# POWER.net
KiCad netlist of a schematic drawn in Altium Designer
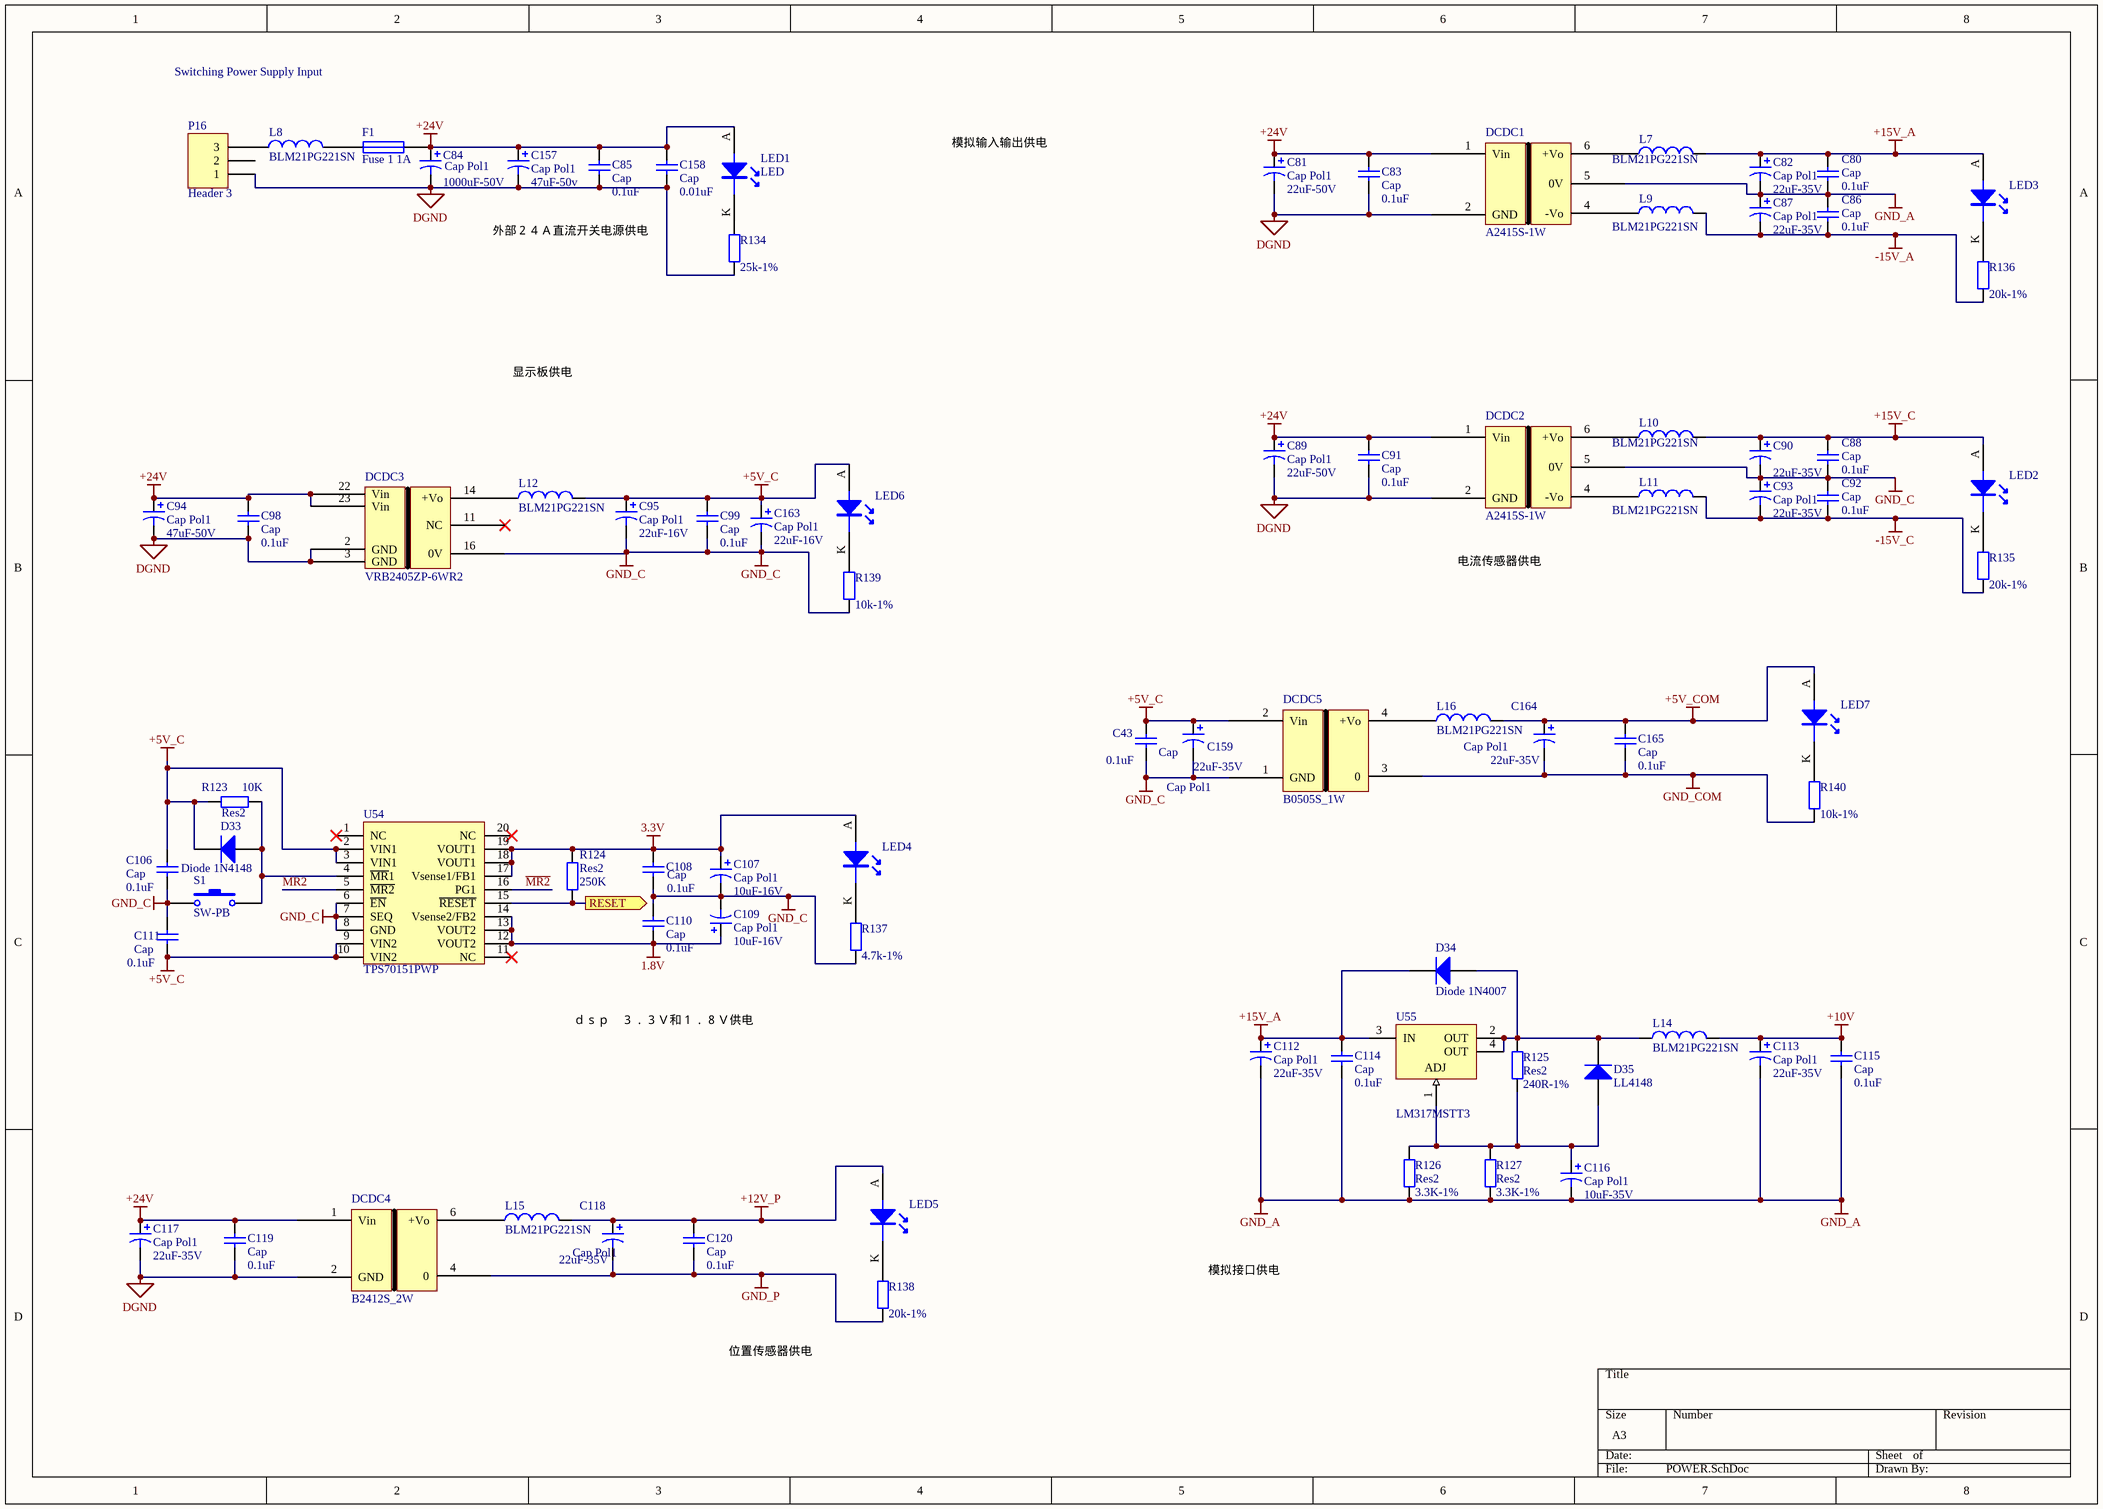
[diagram p0: POWER.SchDoc]

(export (version "E")
  (design (tool "Eeschema 10.0.6"))
  (components
    (comp (ref "C43")
      (value "Cap")
      (footprint "1206")
      (description "Capacitor")
      (fields (field (name "ALTIUM_VALUE") "0.1uF") (field (name "PUBLISHER") "Altium Limited"))
      (libsource (lib "Miscellaneous Devices") (part "Cap"))
    )
    (comp (ref "C80")
      (value "Cap")
      (footprint "1206")
      (description "Capacitor")
      (fields (field (name "ALTIUM_VALUE") "0.1uF") (field (name "PUBLISHER") "Altium Limited"))
      (libsource (lib "Miscellaneous Devices") (part "Cap"))
    )
    (comp (ref "C81")
      (value "Cap Pol1")
      (footprint "7343")
      (description "Polarized Capacitor (Radial)")
      (fields (field (name "ALTIUM_VALUE") "22uF-50V") (field (name "PUBLISHER") "Altium Limited"))
      (libsource (lib "Miscellaneous Devices") (part "Cap Pol1"))
    )
    (comp (ref "C82")
      (value "Cap Pol1")
      (footprint "7343")
      (description "Polarized Capacitor (Radial)")
      (fields (field (name "ALTIUM_VALUE") "22uF-35V") (field (name "PUBLISHER") "Altium Limited"))
      (libsource (lib "Miscellaneous Devices") (part "Cap Pol1"))
    )
    (comp (ref "C83")
      (value "Cap")
      (footprint "1206")
      (description "Capacitor")
      (fields (field (name "ALTIUM_VALUE") "0.1uF") (field (name "PUBLISHER") "Altium Limited"))
      (libsource (lib "Miscellaneous Devices") (part "Cap"))
    )
    (comp (ref "C84")
      (value "Cap Pol1")
      (footprint "电解电容1000uF")
      (description "Polarized Capacitor (Radial)")
      (fields (field (name "ALTIUM_VALUE") "1000uF-50V") (field (name "PUBLISHER") "Altium Limited"))
      (libsource (lib "Miscellaneous Devices") (part "Cap Pol1"))
    )
    (comp (ref "C85")
      (value "Cap")
      (footprint "1206")
      (description "Capacitor")
      (fields (field (name "ALTIUM_VALUE") "0.1uF") (field (name "PUBLISHER") "Altium Limited"))
      (libsource (lib "Miscellaneous Devices") (part "Cap"))
    )
    (comp (ref "C86")
      (value "Cap")
      (footprint "1206")
      (description "Capacitor")
      (fields (field (name "ALTIUM_VALUE") "0.1uF") (field (name "PUBLISHER") "Altium Limited"))
      (libsource (lib "Miscellaneous Devices") (part "Cap"))
    )
    (comp (ref "C87")
      (value "Cap Pol1")
      (footprint "7343")
      (description "Polarized Capacitor (Radial)")
      (fields (field (name "ALTIUM_VALUE") "22uF-35V") (field (name "PUBLISHER") "Altium Limited"))
      (libsource (lib "Miscellaneous Devices") (part "Cap Pol1"))
    )
    (comp (ref "C88")
      (value "Cap")
      (footprint "1206")
      (description "Capacitor")
      (fields (field (name "ALTIUM_VALUE") "0.1uF") (field (name "PUBLISHER") "Altium Limited"))
      (libsource (lib "Miscellaneous Devices") (part "Cap"))
    )
    (comp (ref "C89")
      (value "Cap Pol1")
      (footprint "7343")
      (description "Polarized Capacitor (Radial)")
      (fields (field (name "ALTIUM_VALUE") "22uF-50V") (field (name "PUBLISHER") "Altium Limited"))
      (libsource (lib "Miscellaneous Devices") (part "Cap Pol1"))
    )
    (comp (ref "C90")
      (value "22uF-35V")
      (footprint "7343")
      (description "Polarized Capacitor (Radial)")
      (fields (field (name "Comment") "Cap Pol1") (field (name "PUBLISHER") "Altium Limited"))
      (libsource (lib "Miscellaneous Devices") (part "Cap Pol1"))
    )
    (comp (ref "C91")
      (value "Cap")
      (footprint "1206")
      (description "Capacitor")
      (fields (field (name "ALTIUM_VALUE") "0.1uF") (field (name "PUBLISHER") "Altium Limited"))
      (libsource (lib "Miscellaneous Devices") (part "Cap"))
    )
    (comp (ref "C92")
      (value "Cap")
      (footprint "1206")
      (description "Capacitor")
      (fields (field (name "ALTIUM_VALUE") "0.1uF") (field (name "PUBLISHER") "Altium Limited"))
      (libsource (lib "Miscellaneous Devices") (part "Cap"))
    )
    (comp (ref "C93")
      (value "Cap Pol1")
      (footprint "7343")
      (description "Polarized Capacitor (Radial)")
      (fields (field (name "ALTIUM_VALUE") "22uF-35V") (field (name "PUBLISHER") "Altium Limited"))
      (libsource (lib "Miscellaneous Devices") (part "Cap Pol1"))
    )
    (comp (ref "C94")
      (value "Cap Pol1")
      (footprint "电解电容47uf")
      (description "Polarized Capacitor (Radial)")
      (fields (field (name "ALTIUM_VALUE") "47uF-50V") (field (name "PUBLISHER") "Altium Limited"))
      (libsource (lib "Miscellaneous Devices") (part "Cap Pol1"))
    )
    (comp (ref "C95")
      (value "Cap Pol1")
      (footprint "7343")
      (description "Polarized Capacitor (Radial)")
      (fields (field (name "ALTIUM_VALUE") "22uF-16V") (field (name "PUBLISHER") "Altium Limited"))
      (libsource (lib "Miscellaneous Devices") (part "Cap Pol1"))
    )
    (comp (ref "C98")
      (value "Cap")
      (footprint "1206")
      (description "Capacitor")
      (fields (field (name "ALTIUM_VALUE") "0.1uF") (field (name "PUBLISHER") "Altium Limited"))
      (libsource (lib "Miscellaneous Devices") (part "Cap"))
    )
    (comp (ref "C99")
      (value "Cap")
      (footprint "1206")
      (description "Capacitor")
      (fields (field (name "ALTIUM_VALUE") "0.1uF") (field (name "PUBLISHER") "Altium Limited"))
      (libsource (lib "Miscellaneous Devices") (part "Cap"))
    )
    (comp (ref "C106")
      (value "Cap")
      (footprint "1206")
      (description "Capacitor")
      (fields (field (name "ALTIUM_VALUE") "0.1uF") (field (name "PUBLISHER") "Altium Limited"))
      (libsource (lib "Miscellaneous Devices") (part "Cap"))
    )
    (comp (ref "C107")
      (value "Cap Pol1")
      (footprint "KEMET Electronics Footprints:1206")
      (description "Polarized Capacitor (Radial)")
      (fields (field (name "ALTIUM_VALUE") "10uF-16V") (field (name "PUBLISHER") "Altium Limited"))
      (libsource (lib "Miscellaneous Devices") (part "Cap Pol1"))
    )
    (comp (ref "C108")
      (value "Cap")
      (footprint "1206")
      (description "Capacitor")
      (fields (field (name "ALTIUM_VALUE") "0.1uF") (field (name "PUBLISHER") "Altium Limited"))
      (libsource (lib "Miscellaneous Devices") (part "Cap"))
    )
    (comp (ref "C109")
      (value "Cap Pol1")
      (footprint "KEMET Electronics Footprints:1206")
      (description "Polarized Capacitor (Radial)")
      (fields (field (name "ALTIUM_VALUE") "10uF-16V") (field (name "PUBLISHER") "Altium Limited"))
      (libsource (lib "Miscellaneous Devices") (part "Cap Pol1"))
    )
    (comp (ref "C110")
      (value "Cap")
      (footprint "1206")
      (description "Capacitor")
      (fields (field (name "ALTIUM_VALUE") "0.1uF") (field (name "PUBLISHER") "Altium Limited"))
      (libsource (lib "Miscellaneous Devices") (part "Cap"))
    )
    (comp (ref "C111")
      (value "Cap")
      (footprint "1206")
      (description "Capacitor")
      (fields (field (name "ALTIUM_VALUE") "0.1uF") (field (name "PUBLISHER") "Altium Limited"))
      (libsource (lib "Miscellaneous Devices") (part "Cap"))
    )
    (comp (ref "C112")
      (value "Cap Pol1")
      (footprint "7343")
      (description "Polarized Capacitor (Radial)")
      (fields (field (name "ALTIUM_VALUE") "22uF-35V") (field (name "PUBLISHER") "Altium Limited"))
      (libsource (lib "Miscellaneous Devices") (part "Cap Pol1"))
    )
    (comp (ref "C113")
      (value "Cap Pol1")
      (footprint "7343")
      (description "Polarized Capacitor (Radial)")
      (fields (field (name "ALTIUM_VALUE") "22uF-35V") (field (name "PUBLISHER") "Altium Limited"))
      (libsource (lib "Miscellaneous Devices") (part "Cap Pol1"))
    )
    (comp (ref "C114")
      (value "Cap")
      (footprint "1206")
      (description "Capacitor")
      (fields (field (name "ALTIUM_VALUE") "0.1uF") (field (name "PUBLISHER") "Altium Limited"))
      (libsource (lib "Miscellaneous Devices") (part "Cap"))
    )
    (comp (ref "C115")
      (value "Cap")
      (footprint "1206")
      (description "Capacitor")
      (fields (field (name "ALTIUM_VALUE") "0.1uF") (field (name "PUBLISHER") "Altium Limited"))
      (libsource (lib "Miscellaneous Devices") (part "Cap"))
    )
    (comp (ref "C116")
      (value "Cap Pol1")
      (footprint "KEMET Electronics Footprints:1206")
      (description "Polarized Capacitor (Radial)")
      (fields (field (name "ALTIUM_VALUE") "10uF-35V") (field (name "PUBLISHER") "Altium Limited"))
      (libsource (lib "Miscellaneous Devices") (part "Cap Pol1"))
    )
    (comp (ref "C117")
      (value "Cap Pol1")
      (footprint "7343")
      (description "Polarized Capacitor (Radial)")
      (fields (field (name "ALTIUM_VALUE") "22uF-35V") (field (name "PUBLISHER") "Altium Limited"))
      (libsource (lib "Miscellaneous Devices") (part "Cap Pol1"))
    )
    (comp (ref "C118")
      (value "Cap Pol1")
      (footprint "7343")
      (description "Polarized Capacitor (Radial)")
      (fields (field (name "ALTIUM_VALUE") "22uF-35V") (field (name "PUBLISHER") "Altium Limited"))
      (libsource (lib "Miscellaneous Devices") (part "Cap Pol1"))
    )
    (comp (ref "C119")
      (value "Cap")
      (footprint "1206")
      (description "Capacitor")
      (fields (field (name "ALTIUM_VALUE") "0.1uF") (field (name "PUBLISHER") "Altium Limited"))
      (libsource (lib "Miscellaneous Devices") (part "Cap"))
    )
    (comp (ref "C120")
      (value "Cap")
      (footprint "1206")
      (description "Capacitor")
      (fields (field (name "ALTIUM_VALUE") "0.1uF") (field (name "PUBLISHER") "Altium Limited"))
      (libsource (lib "Miscellaneous Devices") (part "Cap"))
    )
    (comp (ref "C157")
      (value "Cap Pol1")
      (footprint "电解电容47uf")
      (description "Polarized Capacitor (Radial)")
      (fields (field (name "ALTIUM_VALUE") "47uF-50v") (field (name "PUBLISHER") "Altium Limited"))
      (libsource (lib "Miscellaneous Devices") (part "Cap Pol1"))
    )
    (comp (ref "C158")
      (value "Cap")
      (footprint "1206")
      (description "Capacitor")
      (fields (field (name "ALTIUM_VALUE") "0.01uF") (field (name "PUBLISHER") "Altium Limited"))
      (libsource (lib "Miscellaneous Devices") (part "Cap"))
    )
    (comp (ref "C159")
      (value "Cap Pol1")
      (footprint "7343")
      (description "Polarized Capacitor (Radial)")
      (fields (field (name "ALTIUM_VALUE") "22uF-35V") (field (name "PUBLISHER") "Altium Limited"))
      (libsource (lib "Miscellaneous Devices") (part "Cap Pol1"))
    )
    (comp (ref "C163")
      (value "Cap Pol1")
      (footprint "7343")
      (description "Polarized Capacitor (Radial)")
      (fields (field (name "ALTIUM_VALUE") "22uF-16V") (field (name "PUBLISHER") "Altium Limited"))
      (libsource (lib "Miscellaneous Devices") (part "Cap Pol1"))
    )
    (comp (ref "C164")
      (value "Cap Pol1")
      (footprint "7343")
      (description "Polarized Capacitor (Radial)")
      (fields (field (name "ALTIUM_VALUE") "22uF-35V") (field (name "PUBLISHER") "Altium Limited"))
      (libsource (lib "Miscellaneous Devices") (part "Cap Pol1"))
    )
    (comp (ref "C165")
      (value "Cap")
      (footprint "1206")
      (description "Capacitor")
      (fields (field (name "ALTIUM_VALUE") "0.1uF") (field (name "PUBLISHER") "Altium Limited"))
      (libsource (lib "Miscellaneous Devices") (part "Cap"))
    )
    (comp (ref "D33")
      (value "Diode 1N4148")
      (footprint "SOD-80/MLL34")
      (description "High Conductance Fast Diode")
      (fields (field (name "PUBLISHER") "Altium Limited"))
      (libsource (lib "Miscellaneous Devices") (part "Diode 1N4148"))
    )
    (comp (ref "D34")
      (value "Diode 1N4007")
      (footprint "SMA")
      (description "1 Amp General Purpose Rectifier")
      (fields (field (name "PUBLISHER") "Altium Limited"))
      (libsource (lib "Miscellaneous Devices") (part "Diode 1N4007"))
    )
    (comp (ref "D35")
      (value "LL4148")
      (footprint "SMA")
      (description "1 Amp General Purpose Rectifier")
      (fields (field (name "PUBLISHER") "Altium Limited"))
      (libsource (lib "Miscellaneous Devices") (part "Diode 1N4007"))
    )
    (comp (ref "DCDC1")
      (value "A2415S-1W")
      (footprint "Newport Components Footprints:NPSIP7")
      (libsource (lib "Schlib1") (part "A2415S-1W"))
    )
    (comp (ref "DCDC2")
      (value "A2415S-1W")
      (footprint "Newport Components Footprints:NPSIP7")
      (libsource (lib "Schlib1") (part "A2415S-1W"))
    )
    (comp (ref "DCDC3")
      (value "VRB2405ZP-6WR2")
      (footprint "DIP24")
      (libsource (lib "Schlib2") (part "WRB2405ZP-3WR2"))
    )
    (comp (ref "DCDC4")
      (value "B2412S_2W")
      (footprint "PCB21:NPSIP7A_B2412s2")
      (libsource (lib "Schlib1") (part "B2412S_2W"))
    )
    (comp (ref "DCDC5") (value "B0505S_1W") (footprint "B0505") (libsource (lib "Schlib3") (part "newB0505")))
    (comp (ref "F1")
      (value "Fuse 1 1A")
      (footprint "1206")
      (description "Fuse")
      (fields (field (name "PUBLISHER") "Altium Limited"))
      (libsource (lib "Miscellaneous Devices") (part "Fuse 1"))
    )
    (comp (ref "L7")
      (value "BLM21PG221SN")
      (footprint "2012")
      (description "Inductor")
      (fields (field (name "PUBLISHER") "Altium Limited"))
      (libsource (lib "Miscellaneous Devices") (part "Inductor"))
    )
    (comp (ref "L8")
      (value "BLM21PG221SN")
      (footprint "2012")
      (description "Inductor")
      (fields (field (name "PUBLISHER") "Altium Limited"))
      (libsource (lib "Miscellaneous Devices") (part "Inductor"))
    )
    (comp (ref "L9")
      (value "BLM21PG221SN")
      (footprint "2012")
      (description "Inductor")
      (fields (field (name "PUBLISHER") "Altium Limited"))
      (libsource (lib "Miscellaneous Devices") (part "Inductor"))
    )
    (comp (ref "L10")
      (value "BLM21PG221SN")
      (footprint "2012")
      (description "Inductor")
      (fields (field (name "PUBLISHER") "Altium Limited"))
      (libsource (lib "Miscellaneous Devices") (part "Inductor"))
    )
    (comp (ref "L11")
      (value "BLM21PG221SN")
      (footprint "2012")
      (description "Inductor")
      (fields (field (name "PUBLISHER") "Altium Limited"))
      (libsource (lib "Miscellaneous Devices") (part "Inductor"))
    )
    (comp (ref "L12")
      (value "BLM21PG221SN")
      (footprint "2012")
      (description "Inductor")
      (fields (field (name "PUBLISHER") "Altium Limited"))
      (libsource (lib "Miscellaneous Devices") (part "Inductor"))
    )
    (comp (ref "L14")
      (value "BLM21PG221SN")
      (footprint "2012")
      (description "Inductor")
      (fields (field (name "PUBLISHER") "Altium Limited"))
      (libsource (lib "Miscellaneous Devices") (part "Inductor"))
    )
    (comp (ref "L15")
      (value "BLM21PG221SN")
      (footprint "2012")
      (description "Inductor")
      (fields (field (name "PUBLISHER") "Altium Limited"))
      (libsource (lib "Miscellaneous Devices") (part "Inductor"))
    )
    (comp (ref "L16")
      (value "BLM21PG221SN")
      (footprint "2012")
      (description "Inductor")
      (fields (field (name "PUBLISHER") "Altium Limited"))
      (libsource (lib "Miscellaneous Devices") (part "Inductor"))
    )
    (comp (ref "LED1")
      (value "LED")
      (footprint "H040910:0805D")
      (libsource (lib "Miscellaneous Devices") (part "LED"))
    )
    (comp (ref "LED2")
      (value "LED")
      (footprint "H040910:0805D")
      (libsource (lib "Miscellaneous Devices") (part "LED"))
    )
    (comp (ref "LED3")
      (value "LED")
      (footprint "H040910:0805D")
      (libsource (lib "Miscellaneous Devices") (part "LED"))
    )
    (comp (ref "LED4")
      (value "LED")
      (footprint "H040910:0805D")
      (libsource (lib "Miscellaneous Devices") (part "LED"))
    )
    (comp (ref "LED5")
      (value "LED")
      (footprint "H040910:0805D")
      (libsource (lib "Miscellaneous Devices") (part "LED"))
    )
    (comp (ref "LED6")
      (value "LED")
      (footprint "H040910:0805D")
      (libsource (lib "Miscellaneous Devices") (part "LED"))
    )
    (comp (ref "LED7")
      (value "LED")
      (footprint "H040910:0805D")
      (libsource (lib "Miscellaneous Devices") (part "LED"))
    )
    (comp (ref "P16")
      (value "Header 3")
      (footprint "PHENOX-3")
      (description "Header, 3-Pin")
      (fields (field (name "PUBLISHER") "Altium Limited"))
      (libsource (lib "Miscellaneous Connectors") (part "Header 3"))
    )
    (comp (ref "R123")
      (value "Res2")
      (footprint "1206")
      (description "Resistor")
      (fields (field (name "ALTIUM_VALUE") "10K") (field (name "PUBLISHER") "Altium Limited"))
      (libsource (lib "") (part "Res2_1"))
    )
    (comp (ref "R124")
      (value "Res2")
      (footprint "1206")
      (description "Resistor")
      (fields (field (name "ALTIUM_VALUE") "250K") (field (name "PUBLISHER") "Altium Limited"))
      (libsource (lib "Miscellaneous Devices") (part "Res2"))
    )
    (comp (ref "R125")
      (value "Res2")
      (footprint "1206")
      (description "Resistor")
      (fields (field (name "ALTIUM_VALUE") "240R-1%") (field (name "PUBLISHER") "Altium Limited"))
      (libsource (lib "Miscellaneous Devices") (part "Res2"))
    )
    (comp (ref "R126")
      (value "Res2")
      (footprint "1206")
      (description "Resistor")
      (fields (field (name "ALTIUM_VALUE") "3.3K-1%") (field (name "PUBLISHER") "Altium Limited"))
      (libsource (lib "Miscellaneous Devices") (part "Res2"))
    )
    (comp (ref "R127")
      (value "Res2")
      (footprint "1206")
      (description "Resistor")
      (fields (field (name "ALTIUM_VALUE") "3.3K-1%") (field (name "PUBLISHER") "Altium Limited"))
      (libsource (lib "Miscellaneous Devices") (part "Res2"))
    )
    (comp (ref "R134")
      (value "25k-1%")
      (footprint "1206")
      (description "Resistor")
      (fields (field (name "Comment") "Res2") (field (name "PUBLISHER") "Altium Limited"))
      (libsource (lib "Miscellaneous Devices") (part "Res2"))
    )
    (comp (ref "R135")
      (value "20k-1%")
      (footprint "1206")
      (description "Resistor")
      (fields (field (name "Comment") "Res2") (field (name "PUBLISHER") "Altium Limited"))
      (libsource (lib "Miscellaneous Devices") (part "Res2"))
    )
    (comp (ref "R136")
      (value "20k-1%")
      (footprint "1206")
      (description "Resistor")
      (fields (field (name "Comment") "Res2") (field (name "PUBLISHER") "Altium Limited"))
      (libsource (lib "Miscellaneous Devices") (part "Res2"))
    )
    (comp (ref "R137")
      (value "4.7k-1%")
      (footprint "1206")
      (description "Resistor")
      (fields (field (name "Comment") "Res2") (field (name "PUBLISHER") "Altium Limited"))
      (libsource (lib "Miscellaneous Devices") (part "Res2"))
    )
    (comp (ref "R138")
      (value "20k-1%")
      (footprint "1206")
      (description "Resistor")
      (fields (field (name "Comment") "Res2") (field (name "PUBLISHER") "Altium Limited"))
      (libsource (lib "Miscellaneous Devices") (part "Res2"))
    )
    (comp (ref "R139")
      (value "10k-1%")
      (footprint "1206")
      (description "Resistor")
      (fields (field (name "Comment") "Res2") (field (name "PUBLISHER") "Altium Limited"))
      (libsource (lib "Miscellaneous Devices") (part "Res2"))
    )
    (comp (ref "R140")
      (value "10k-1%")
      (footprint "1206")
      (description "Resistor")
      (fields (field (name "Comment") "Res2") (field (name "PUBLISHER") "Altium Limited"))
      (libsource (lib "Miscellaneous Devices") (part "Res2"))
    )
    (comp (ref "S1")
      (value "SW-PB")
      (footprint "B3F4050")
      (description "Switch")
      (fields (field (name "PUBLISHER") "Altium Limited"))
      (libsource (lib "Miscellaneous Devices") (part "SW-PB"))
    )
    (comp (ref "U54")
      (value "TPS70151PWP")
      (footprint "tssop20")
      (libsource (lib "Schlib2") (part "TPS70151PWP"))
    )
    (comp (ref "U55")
      (value "LM317MSTT3")
      (footprint "SOT223-4N")
      (description "Three-Terminal Adjustable Output Positive Voltage Regulator")
      (fields (field (name "PUBLISHER") "Altium Limited"))
      (libsource (lib "ON Semi Power Mgt Voltage Regulator_1") (part "LM317MSTT3"))
    )
  )
  (nets
    (net (code "1") (name "+5V_C") (class "Default")
      (node (ref "C106") (pin "2") (pinfunction "2_2") (pintype "passive"))
      (node (ref "C111") (pin "1") (pinfunction "1_1") (pintype "passive"))
      (node (ref "C159") (pin "1") (pinfunction "1_1") (pintype "passive"))
      (node (ref "C163") (pin "1") (pinfunction "1_1") (pintype "passive"))
      (node (ref "C43") (pin "2") (pinfunction "2_2") (pintype "passive"))
      (node (ref "C95") (pin "1") (pinfunction "1_1") (pintype "passive"))
      (node (ref "C99") (pin "2") (pinfunction "2_2") (pintype "passive"))
      (node (ref "D33") (pin "2") (pinfunction "K_2") (pintype "passive"))
      (node (ref "DCDC5") (pin "2") (pinfunction "Vin_2") (pintype "passive"))
      (node (ref "L12") (pin "2") (pinfunction "2_2") (pintype "passive"))
      (node (ref "LED6") (pin "A") (pinfunction "1_A") (pintype "passive"))
      (node (ref "R123") (pin "2") (pinfunction "2_2") (pintype "passive"))
      (node (ref "U54") (pin "10") (pinfunction "VIN2_10") (pintype "passive"))
      (node (ref "U54") (pin "2") (pinfunction "VIN1_2") (pintype "passive"))
      (node (ref "U54") (pin "3") (pinfunction "VIN1_3") (pintype "passive"))
      (node (ref "U54") (pin "9") (pinfunction "VIN2_9") (pintype "passive"))
    )
    (net (code "2") (name "+5V_COM") (class "Default")
      (node (ref "C164") (pin "1") (pinfunction "1_1") (pintype "passive"))
      (node (ref "C165") (pin "2") (pinfunction "2_2") (pintype "passive"))
      (node (ref "L16") (pin "2") (pinfunction "2_2") (pintype "passive"))
      (node (ref "LED7") (pin "A") (pinfunction "1_A") (pintype "passive"))
    )
    (net (code "3") (name "+10V") (class "Default")
      (node (ref "C113") (pin "1") (pinfunction "1_1") (pintype "passive"))
      (node (ref "C115") (pin "2") (pinfunction "2_2") (pintype "passive"))
      (node (ref "L14") (pin "2") (pinfunction "2_2") (pintype "passive"))
    )
    (net (code "4") (name "+12V_P") (class "Default")
      (node (ref "C118") (pin "1") (pinfunction "1_1") (pintype "passive"))
      (node (ref "C120") (pin "2") (pinfunction "2_2") (pintype "passive"))
      (node (ref "L15") (pin "2") (pinfunction "2_2") (pintype "passive"))
      (node (ref "LED5") (pin "A") (pinfunction "1_A") (pintype "passive"))
    )
    (net (code "5") (name "+15V_A") (class "Default")
      (node (ref "C112") (pin "1") (pinfunction "1_1") (pintype "passive"))
      (node (ref "C114") (pin "2") (pinfunction "2_2") (pintype "passive"))
      (node (ref "C80") (pin "2") (pinfunction "2_2") (pintype "passive"))
      (node (ref "C82") (pin "1") (pinfunction "1_1") (pintype "passive"))
      (node (ref "D34") (pin "2") (pinfunction "K_2") (pintype "passive"))
      (node (ref "L7") (pin "2") (pinfunction "2_2") (pintype "passive"))
      (node (ref "LED3") (pin "A") (pinfunction "1_A") (pintype "passive"))
      (node (ref "U55") (pin "3") (pinfunction "IN_3") (pintype "power_in"))
    )
    (net (code "6") (name "+15V_C") (class "Default")
      (node (ref "C88") (pin "2") (pinfunction "2_2") (pintype "passive"))
      (node (ref "C90") (pin "1") (pinfunction "1_1") (pintype "passive"))
      (node (ref "L10") (pin "2") (pinfunction "2_2") (pintype "passive"))
      (node (ref "LED2") (pin "A") (pinfunction "1_A") (pintype "passive"))
    )
    (net (code "7") (name "+24V") (class "Default")
      (node (ref "C117") (pin "1") (pinfunction "1_1") (pintype "passive"))
      (node (ref "C119") (pin "2") (pinfunction "2_2") (pintype "passive"))
      (node (ref "C157") (pin "1") (pinfunction "1_1") (pintype "passive"))
      (node (ref "C158") (pin "1") (pinfunction "1_1") (pintype "passive"))
      (node (ref "C81") (pin "1") (pinfunction "1_1") (pintype "passive"))
      (node (ref "C83") (pin "2") (pinfunction "2_2") (pintype "passive"))
      (node (ref "C84") (pin "1") (pinfunction "1_1") (pintype "passive"))
      (node (ref "C85") (pin "2") (pinfunction "2_2") (pintype "passive"))
      (node (ref "C89") (pin "1") (pinfunction "1_1") (pintype "passive"))
      (node (ref "C91") (pin "2") (pinfunction "2_2") (pintype "passive"))
      (node (ref "C94") (pin "1") (pinfunction "1_1") (pintype "passive"))
      (node (ref "C98") (pin "2") (pinfunction "2_2") (pintype "passive"))
      (node (ref "DCDC1") (pin "1") (pinfunction "Vin_1") (pintype "passive"))
      (node (ref "DCDC2") (pin "1") (pinfunction "Vin_1") (pintype "passive"))
      (node (ref "DCDC3") (pin "22") (pinfunction "Vin_22") (pintype "passive"))
      (node (ref "DCDC3") (pin "23") (pinfunction "Vin_23") (pintype "passive"))
      (node (ref "DCDC4") (pin "1") (pinfunction "Vin_1") (pintype "passive"))
      (node (ref "F1") (pin "2") (pinfunction "2_2") (pintype "passive"))
      (node (ref "LED1") (pin "A") (pinfunction "1_A") (pintype "passive"))
    )
    (net (code "8") (name "-15V_A") (class "Default")
      (node (ref "C86") (pin "1") (pinfunction "1_1") (pintype "passive"))
      (node (ref "C87") (pin "2") (pinfunction "2_2") (pintype "passive"))
      (node (ref "L9") (pin "2") (pinfunction "2_2") (pintype "passive"))
      (node (ref "R136") (pin "1") (pinfunction "1_1") (pintype "passive"))
    )
    (net (code "9") (name "-15V_C") (class "Default")
      (node (ref "C92") (pin "1") (pinfunction "1_1") (pintype "passive"))
      (node (ref "C93") (pin "2") (pinfunction "2_2") (pintype "passive"))
      (node (ref "L11") (pin "2") (pinfunction "2_2") (pintype "passive"))
      (node (ref "R135") (pin "1") (pinfunction "1_1") (pintype "passive"))
    )
    (net (code "10") (name "/RESET") (class "Default")
      (node (ref "R124") (pin "1") (pinfunction "1_1") (pintype "passive"))
      (node (ref "U54") (pin "15") (pinfunction "~{RESET}_15") (pintype "passive"))
    )
    (net (code "11") (name "/~{MR2}") (class "Default")
      (node (ref "U54") (pin "16") (pinfunction "PG1_16") (pintype "passive"))
      (node (ref "U54") (pin "5") (pinfunction "~{MR2}_5") (pintype "passive"))
    )
    (net (code "12") (name "1.8V") (class "Default")
      (node (ref "C109") (pin "1") (pinfunction "1_1") (pintype "passive"))
      (node (ref "C110") (pin "1") (pinfunction "1_1") (pintype "passive"))
      (node (ref "U54") (pin "12") (pinfunction "VOUT2_12") (pintype "passive"))
      (node (ref "U54") (pin "13") (pinfunction "VOUT2_13") (pintype "passive"))
      (node (ref "U54") (pin "14") (pinfunction "Vsense2/FB2_14") (pintype "passive"))
    )
    (net (code "13") (name "3.3V") (class "Default")
      (node (ref "C107") (pin "1") (pinfunction "1_1") (pintype "passive"))
      (node (ref "C108") (pin "2") (pinfunction "2_2") (pintype "passive"))
      (node (ref "LED4") (pin "A") (pinfunction "1_A") (pintype "passive"))
      (node (ref "R124") (pin "2") (pinfunction "2_2") (pintype "passive"))
      (node (ref "U54") (pin "17") (pinfunction "Vsense1/FB1_17") (pintype "passive"))
      (node (ref "U54") (pin "18") (pinfunction "VOUT1_18") (pintype "passive"))
      (node (ref "U54") (pin "19") (pinfunction "VOUT1_19") (pintype "passive"))
    )
    (net (code "14") (name "DGND") (class "Default")
      (node (ref "C117") (pin "2") (pinfunction "2_2") (pintype "passive"))
      (node (ref "C119") (pin "1") (pinfunction "1_1") (pintype "passive"))
      (node (ref "C157") (pin "2") (pinfunction "2_2") (pintype "passive"))
      (node (ref "C158") (pin "2") (pinfunction "2_2") (pintype "passive"))
      (node (ref "C81") (pin "2") (pinfunction "2_2") (pintype "passive"))
      (node (ref "C83") (pin "1") (pinfunction "1_1") (pintype "passive"))
      (node (ref "C84") (pin "2") (pinfunction "2_2") (pintype "passive"))
      (node (ref "C85") (pin "1") (pinfunction "1_1") (pintype "passive"))
      (node (ref "C89") (pin "2") (pinfunction "2_2") (pintype "passive"))
      (node (ref "C91") (pin "1") (pinfunction "1_1") (pintype "passive"))
      (node (ref "C94") (pin "2") (pinfunction "2_2") (pintype "passive"))
      (node (ref "C98") (pin "1") (pinfunction "1_1") (pintype "passive"))
      (node (ref "DCDC1") (pin "2") (pinfunction "GND_2") (pintype "passive"))
      (node (ref "DCDC2") (pin "2") (pinfunction "GND_2") (pintype "passive"))
      (node (ref "DCDC3") (pin "2") (pinfunction "GND_2") (pintype "passive"))
      (node (ref "DCDC3") (pin "3") (pinfunction "GND_3") (pintype "passive"))
      (node (ref "DCDC4") (pin "2") (pinfunction "GND_2") (pintype "passive"))
      (node (ref "P16") (pin "1") (pinfunction "1_1") (pintype "passive"))
      (node (ref "R134") (pin "1") (pinfunction "1_1") (pintype "passive"))
    )
    (net (code "15") (name "GND_A") (class "Default")
      (node (ref "C112") (pin "2") (pinfunction "2_2") (pintype "passive"))
      (node (ref "C113") (pin "2") (pinfunction "2_2") (pintype "passive"))
      (node (ref "C114") (pin "1") (pinfunction "1_1") (pintype "passive"))
      (node (ref "C115") (pin "1") (pinfunction "1_1") (pintype "passive"))
      (node (ref "C116") (pin "2") (pinfunction "2_2") (pintype "passive"))
      (node (ref "C80") (pin "1") (pinfunction "1_1") (pintype "passive"))
      (node (ref "C82") (pin "2") (pinfunction "2_2") (pintype "passive"))
      (node (ref "C86") (pin "2") (pinfunction "2_2") (pintype "passive"))
      (node (ref "C87") (pin "1") (pinfunction "1_1") (pintype "passive"))
      (node (ref "DCDC1") (pin "5") (pinfunction "0V_5") (pintype "passive"))
      (node (ref "R126") (pin "1") (pinfunction "1_1") (pintype "passive"))
      (node (ref "R127") (pin "1") (pinfunction "1_1") (pintype "passive"))
    )
    (net (code "16") (name "GND_C") (class "Default")
      (node (ref "C106") (pin "1") (pinfunction "1_1") (pintype "passive"))
      (node (ref "C107") (pin "2") (pinfunction "2_2") (pintype "passive"))
      (node (ref "C108") (pin "1") (pinfunction "1_1") (pintype "passive"))
      (node (ref "C109") (pin "2") (pinfunction "2_2") (pintype "passive"))
      (node (ref "C110") (pin "2") (pinfunction "2_2") (pintype "passive"))
      (node (ref "C111") (pin "2") (pinfunction "2_2") (pintype "passive"))
      (node (ref "C159") (pin "2") (pinfunction "2_2") (pintype "passive"))
      (node (ref "C163") (pin "2") (pinfunction "2_2") (pintype "passive"))
      (node (ref "C43") (pin "1") (pinfunction "1_1") (pintype "passive"))
      (node (ref "C88") (pin "1") (pinfunction "1_1") (pintype "passive"))
      (node (ref "C90") (pin "2") (pinfunction "2_2") (pintype "passive"))
      (node (ref "C92") (pin "2") (pinfunction "2_2") (pintype "passive"))
      (node (ref "C93") (pin "1") (pinfunction "1_1") (pintype "passive"))
      (node (ref "C95") (pin "2") (pinfunction "2_2") (pintype "passive"))
      (node (ref "C99") (pin "1") (pinfunction "1_1") (pintype "passive"))
      (node (ref "DCDC2") (pin "5") (pinfunction "0V_5") (pintype "passive"))
      (node (ref "DCDC3") (pin "16") (pinfunction "0V_16") (pintype "passive"))
      (node (ref "DCDC5") (pin "1") (pinfunction "GND_1") (pintype "passive"))
      (node (ref "R137") (pin "1") (pinfunction "1_1") (pintype "passive"))
      (node (ref "R139") (pin "1") (pinfunction "1_1") (pintype "passive"))
      (node (ref "S1") (pin "1") (pinfunction "1_1") (pintype "passive"))
      (node (ref "U54") (pin "6") (pinfunction "~{EN}_6") (pintype "passive"))
      (node (ref "U54") (pin "7") (pinfunction "SEQ_7") (pintype "passive"))
      (node (ref "U54") (pin "8") (pinfunction "GND_8") (pintype "passive"))
    )
    (net (code "17") (name "GND_COM") (class "Default")
      (node (ref "C164") (pin "2") (pinfunction "2_2") (pintype "passive"))
      (node (ref "C165") (pin "1") (pinfunction "1_1") (pintype "passive"))
      (node (ref "DCDC5") (pin "3") (pinfunction "0_3") (pintype "passive"))
      (node (ref "R140") (pin "1") (pinfunction "1_1") (pintype "passive"))
    )
    (net (code "18") (name "GND_P") (class "Default")
      (node (ref "C118") (pin "2") (pinfunction "2_2") (pintype "passive"))
      (node (ref "C120") (pin "1") (pinfunction "1_1") (pintype "passive"))
      (node (ref "DCDC4") (pin "4") (pinfunction "0_4") (pintype "passive"))
      (node (ref "R138") (pin "1") (pinfunction "1_1") (pintype "passive"))
    )
    (net (code "19") (name "Net-(D33-A)") (class "Default")
      (node (ref "D33") (pin "1") (pinfunction "A_1") (pintype "passive"))
      (node (ref "R123") (pin "1") (pinfunction "1_1") (pintype "passive"))
      (node (ref "S1") (pin "2") (pinfunction "2_2") (pintype "passive"))
      (node (ref "U54") (pin "4") (pinfunction "~{MR}1_4") (pintype "passive"))
    )
    (net (code "20") (name "Net-(D34-A)") (class "Default")
      (node (ref "D34") (pin "1") (pinfunction "A_1") (pintype "passive"))
      (node (ref "D35") (pin "2") (pinfunction "K_2") (pintype "passive"))
      (node (ref "L14") (pin "1") (pinfunction "1_1") (pintype "passive"))
      (node (ref "R125") (pin "2") (pinfunction "2_2") (pintype "passive"))
      (node (ref "U55") (pin "2") (pinfunction "OUT_2") (pintype "power_in"))
      (node (ref "U55") (pin "4") (pinfunction "OUT_4") (pintype "power_in"))
    )
    (net (code "21") (name "Net-(D35-A)") (class "Default")
      (node (ref "C116") (pin "1") (pinfunction "1_1") (pintype "passive"))
      (node (ref "D35") (pin "1") (pinfunction "A_1") (pintype "passive"))
      (node (ref "R125") (pin "1") (pinfunction "1_1") (pintype "passive"))
      (node (ref "R126") (pin "2") (pinfunction "2_2") (pintype "passive"))
      (node (ref "R127") (pin "2") (pinfunction "2_2") (pintype "passive"))
      (node (ref "U55") (pin "1") (pinfunction "ADJ_1") (pintype "input"))
    )
    (net (code "22") (name "Net-(DCDC1-+Vo)") (class "Default")
      (node (ref "DCDC1") (pin "6") (pinfunction "+Vo_6") (pintype "passive"))
      (node (ref "L7") (pin "1") (pinfunction "1_1") (pintype "passive"))
    )
    (net (code "23") (name "Net-(DCDC1--Vo)") (class "Default")
      (node (ref "DCDC1") (pin "4") (pinfunction "-Vo_4") (pintype "passive"))
      (node (ref "L9") (pin "1") (pinfunction "1_1") (pintype "passive"))
    )
    (net (code "24") (name "Net-(DCDC2-+Vo)") (class "Default")
      (node (ref "DCDC2") (pin "6") (pinfunction "+Vo_6") (pintype "passive"))
      (node (ref "L10") (pin "1") (pinfunction "1_1") (pintype "passive"))
    )
    (net (code "25") (name "Net-(DCDC2--Vo)") (class "Default")
      (node (ref "DCDC2") (pin "4") (pinfunction "-Vo_4") (pintype "passive"))
      (node (ref "L11") (pin "1") (pinfunction "1_1") (pintype "passive"))
    )
    (net (code "26") (name "Net-(DCDC3-+Vo)") (class "Default")
      (node (ref "DCDC3") (pin "14") (pinfunction "+Vo_14") (pintype "passive"))
      (node (ref "L12") (pin "1") (pinfunction "1_1") (pintype "passive"))
    )
    (net (code "27") (name "Net-(DCDC4-+Vo)") (class "Default")
      (node (ref "DCDC4") (pin "6") (pinfunction "+Vo_6") (pintype "passive"))
      (node (ref "L15") (pin "1") (pinfunction "1_1") (pintype "passive"))
    )
    (net (code "28") (name "Net-(DCDC5-+Vo)") (class "Default")
      (node (ref "DCDC5") (pin "4") (pinfunction "+Vo_4") (pintype "passive"))
      (node (ref "L16") (pin "1") (pinfunction "1_1") (pintype "passive"))
    )
    (net (code "29") (name "Net-(F1-Pad1)") (class "Default")
      (node (ref "F1") (pin "1") (pinfunction "1_1") (pintype "passive"))
      (node (ref "L8") (pin "2") (pinfunction "2_2") (pintype "passive"))
    )
    (net (code "30") (name "Net-(L8-Pad1)") (class "Default")
      (node (ref "L8") (pin "1") (pinfunction "1_1") (pintype "passive"))
      (node (ref "P16") (pin "3") (pinfunction "3_3") (pintype "passive"))
    )
    (net (code "31") (name "Net-(LED1-2)") (class "Default")
      (node (ref "LED1") (pin "K") (pinfunction "2_K") (pintype "passive"))
      (node (ref "R134") (pin "2") (pinfunction "2_2") (pintype "passive"))
    )
    (net (code "32") (name "Net-(LED2-2)") (class "Default")
      (node (ref "LED2") (pin "K") (pinfunction "2_K") (pintype "passive"))
      (node (ref "R135") (pin "2") (pinfunction "2_2") (pintype "passive"))
    )
    (net (code "33") (name "Net-(LED3-2)") (class "Default")
      (node (ref "LED3") (pin "K") (pinfunction "2_K") (pintype "passive"))
      (node (ref "R136") (pin "2") (pinfunction "2_2") (pintype "passive"))
    )
    (net (code "34") (name "Net-(LED4-2)") (class "Default")
      (node (ref "LED4") (pin "K") (pinfunction "2_K") (pintype "passive"))
      (node (ref "R137") (pin "2") (pinfunction "2_2") (pintype "passive"))
    )
    (net (code "35") (name "Net-(LED5-2)") (class "Default")
      (node (ref "LED5") (pin "K") (pinfunction "2_K") (pintype "passive"))
      (node (ref "R138") (pin "2") (pinfunction "2_2") (pintype "passive"))
    )
    (net (code "36") (name "Net-(LED6-2)") (class "Default")
      (node (ref "LED6") (pin "K") (pinfunction "2_K") (pintype "passive"))
      (node (ref "R139") (pin "2") (pinfunction "2_2") (pintype "passive"))
    )
    (net (code "37") (name "Net-(LED7-2)") (class "Default")
      (node (ref "LED7") (pin "K") (pinfunction "2_K") (pintype "passive"))
      (node (ref "R140") (pin "2") (pinfunction "2_2") (pintype "passive"))
    )
    (net (code "38") (name "unconnected-(DCDC3-NC-Pad11)") (class "Default")
      (node (ref "DCDC3") (pin "11") (pinfunction "NC_11") (pintype "passive+no_connect"))
    )
    (net (code "39") (name "unconnected-(P16-Pad2)") (class "Default")
      (node (ref "P16") (pin "2") (pinfunction "2_2") (pintype "passive"))
    )
    (net (code "40") (name "unconnected-(U54-NC-Pad1)") (class "Default")
      (node (ref "U54") (pin "1") (pinfunction "NC_1") (pintype "passive+no_connect"))
    )
    (net (code "41") (name "unconnected-(U54-NC-Pad11)") (class "Default")
      (node (ref "U54") (pin "11") (pinfunction "NC_11") (pintype "passive+no_connect"))
    )
    (net (code "42") (name "unconnected-(U54-NC-Pad20)") (class "Default")
      (node (ref "U54") (pin "20") (pinfunction "NC_20") (pintype "passive+no_connect"))
    )
  )
)
